# I2C-PullUps.net
KiCad netlist of a schematic drawn in Altium Designer
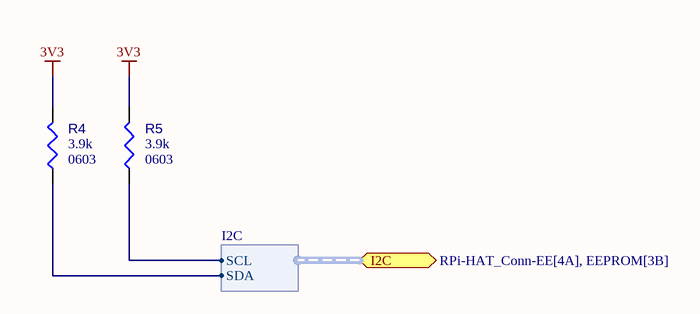
[diagram p0: I2C-PullUps.SchDoc]

(export (version "E")
  (design (tool "Eeschema 10.0.6"))
  (components
    (comp (ref "R4")
      (value "3.9k")
      (footprint "RESC1608X55X25ML10T15")
      (description "Chip Resistor, 1 KOhm, +/-1%, 0.1 W, -55 to 155 degC, 0603 (1608 Metric)")
      (fields
        (field (name "CASE/PACKAGE") "0603")
        (field (name "POWER") "100mW")
        (field (name "TOLERANCE") "1%")
      )
      (libsource (lib "Twill Technology Inc") (part "RES-2"))
    )
    (comp (ref "R5")
      (value "3.9k")
      (footprint "RESC1608X55X25ML10T15")
      (description "Chip Resistor, 1 KOhm, +/-1%, 0.1 W, -55 to 155 degC, 0603 (1608 Metric)")
      (fields
        (field (name "CASE/PACKAGE") "0603")
        (field (name "POWER") "100mW")
        (field (name "TOLERANCE") "1%")
      )
      (libsource (lib "Twill Technology Inc") (part "RES-2"))
    )
  )
  (nets
    (net (code "2") (name "/SCL") (class "Default")
      (node (ref "R5") (pin "1") (pinfunction "1_1") (pintype "passive"))
    )
    (net (code "3") (name "/SDA") (class "Default")
      (node (ref "R4") (pin "1") (pinfunction "1_1") (pintype "passive"))
    )
    (net (code "5") (name "3V3") (class "Default")
      (node (ref "R4") (pin "2") (pinfunction "2_2") (pintype "passive"))
      (node (ref "R5") (pin "2") (pinfunction "2_2") (pintype "passive"))
    )
  )
)
